# RelayBoard2.net
KiCad netlist of a schematic drawn in EAGLE
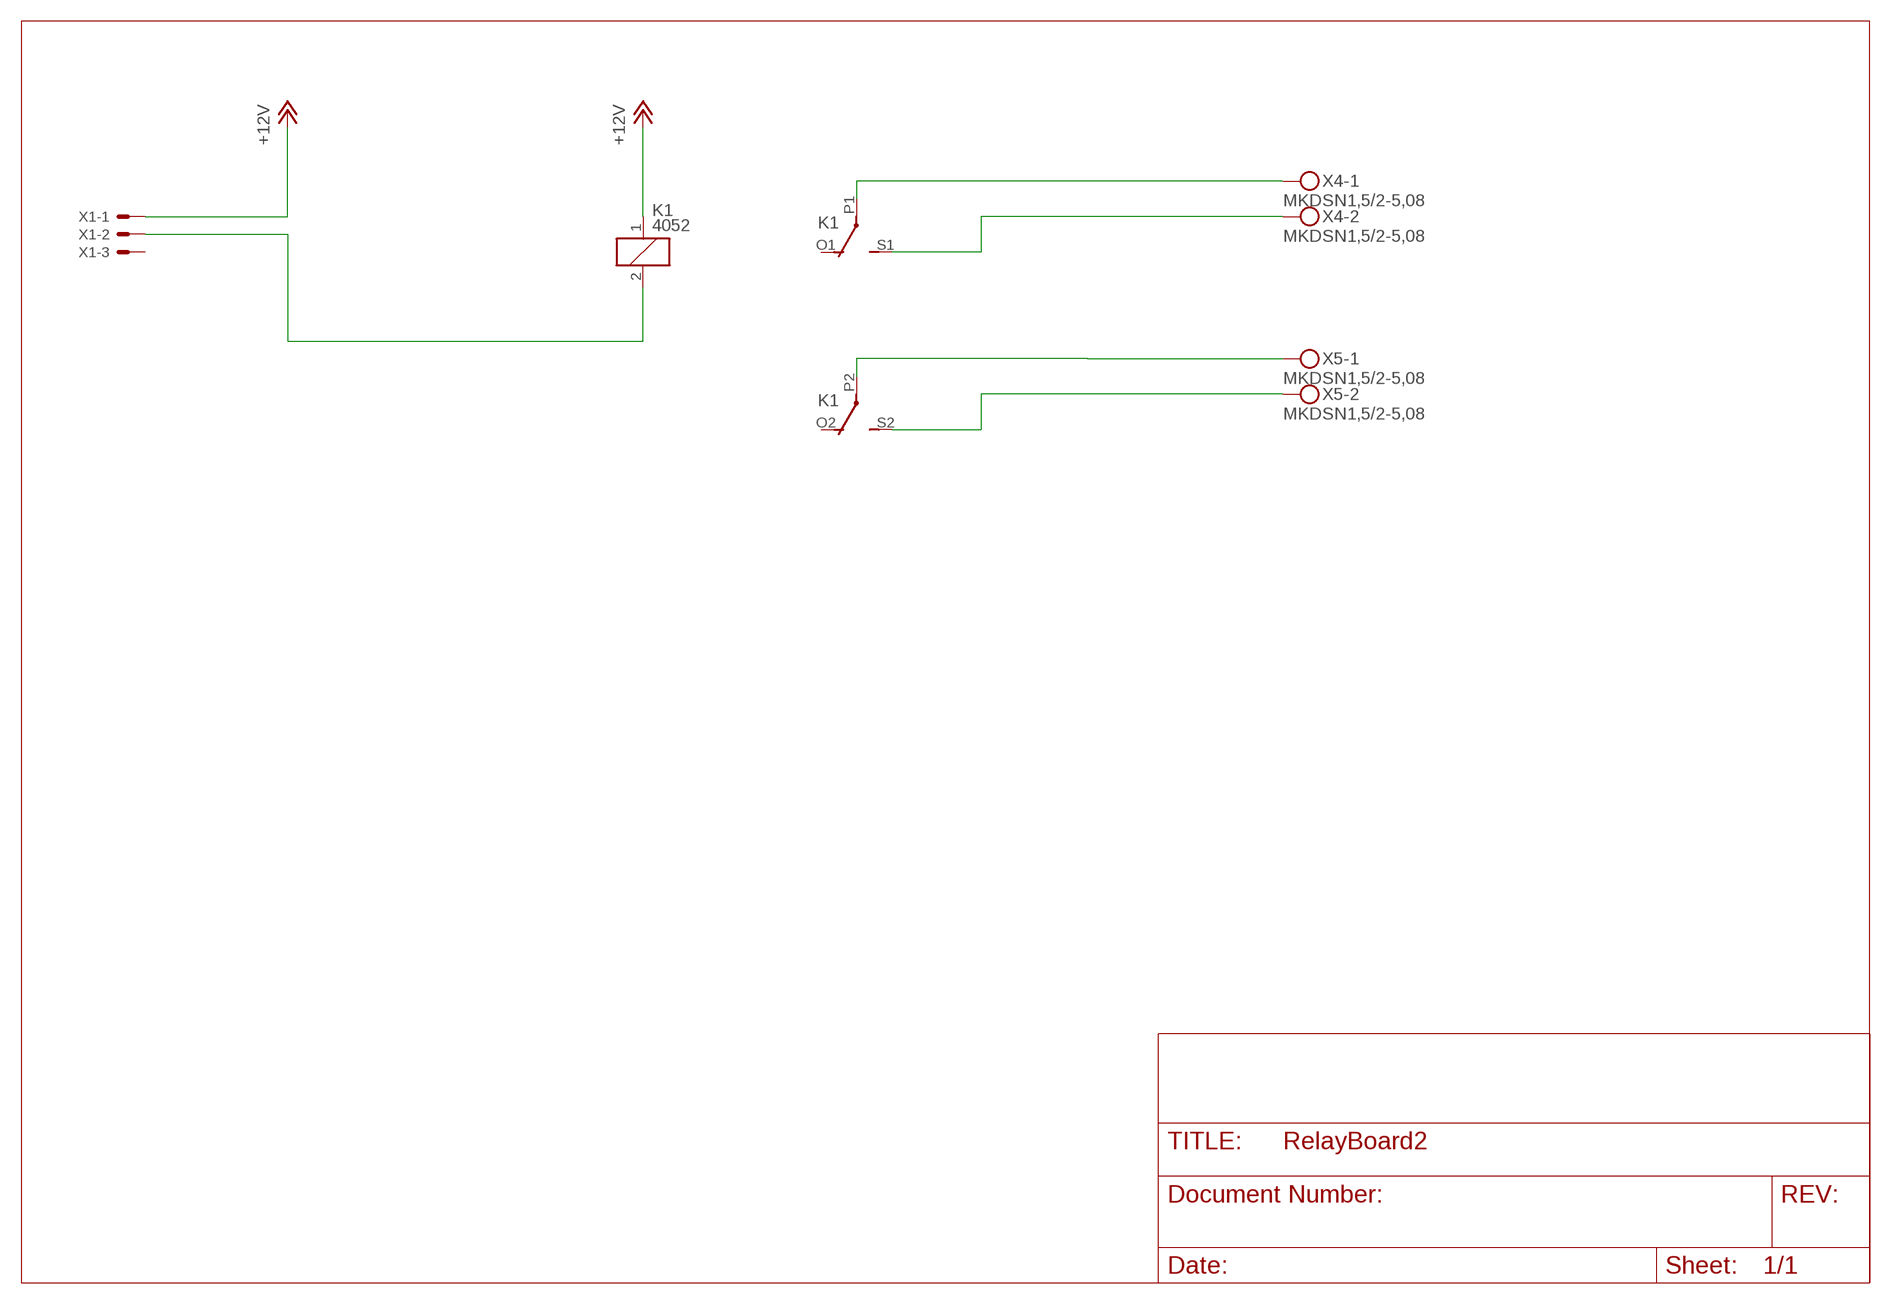
[diagram p0: schematic, sheet 1]

(export (version "E")
  (design (tool "Eeschema 10.0.6"))
  (components
    (comp (ref "K1")
      (value "4052")
      (footprint "eagle-import:F4052")
      (libsource (lib "eagle-import") (part "4052"))
    )
    (comp (ref "X1")
      (value "KK-156-3")
      (footprint "eagle-import:KK-156-3")
      (libsource (lib "eagle-import") (part "KK-156-3"))
    )
    (comp (ref "X4")
      (value "MKDSN1,5/2-5,08")
      (footprint "eagle-import:MKDSN1,5_2-5,08")
      (fields (field (name "MPN") "MKDSN 1,5/2-5.08"))
      (libsource (lib "eagle-import") (part "MKDSN1,5/2-5,08"))
    )
    (comp (ref "X5")
      (value "MKDSN1,5/2-5,08")
      (footprint "eagle-import:MKDSN1,5_2-5,08")
      (fields (field (name "MPN") "MKDSN 1,5/2-5.08"))
      (libsource (lib "eagle-import") (part "MKDSN1,5/2-5,08"))
    )
  )
  (nets
    (net (code "1") (name "+12V") (class "Default")
      (node (ref "K1") (pin "1") (pinfunction "1_1") (pintype "passive"))
      (node (ref "X1") (pin "1") (pinfunction "S_1") (pintype "passive"))
    )
    (net (code "2") (name "Net-(K1B-P)") (class "Default")
      (node (ref "K1") (pin "P1") (pinfunction "P_P1") (pintype "passive"))
      (node (ref "X4") (pin "1") (pinfunction "KL_1") (pintype "passive"))
    )
    (net (code "3") (name "Net-(K1B-S)") (class "Default")
      (node (ref "K1") (pin "S1") (pinfunction "S_S1") (pintype "passive"))
      (node (ref "X4") (pin "2") (pinfunction "KL_2") (pintype "passive"))
    )
    (net (code "4") (name "Net-(K1C-P)") (class "Default")
      (node (ref "K1") (pin "P2") (pinfunction "P_P2") (pintype "passive"))
      (node (ref "X5") (pin "1") (pinfunction "KL_1") (pintype "passive"))
    )
    (net (code "5") (name "Net-(K1C-S)") (class "Default")
      (node (ref "K1") (pin "S2") (pinfunction "S_S2") (pintype "passive"))
      (node (ref "X5") (pin "2") (pinfunction "KL_2") (pintype "passive"))
    )
    (net (code "6") (name "Net-(X1B-S)") (class "Default")
      (node (ref "K1") (pin "2") (pinfunction "2_2") (pintype "passive"))
      (node (ref "X1") (pin "2") (pinfunction "S_2") (pintype "passive"))
    )
    (net (code "7") (name "unconnected-(K1B-O-PadO1)") (class "Default")
      (node (ref "K1") (pin "O1") (pinfunction "O_O1") (pintype "passive"))
    )
    (net (code "8") (name "unconnected-(K1C-O-PadO2)") (class "Default")
      (node (ref "K1") (pin "O2") (pinfunction "O_O2") (pintype "passive"))
    )
    (net (code "9") (name "unconnected-(X1C-S-Pad3)") (class "Default")
      (node (ref "X1") (pin "3") (pinfunction "S_3") (pintype "passive"))
    )
  )
)
